# Cree_4x4_Led_Panel.net
KiCad netlist of a schematic drawn in EAGLE
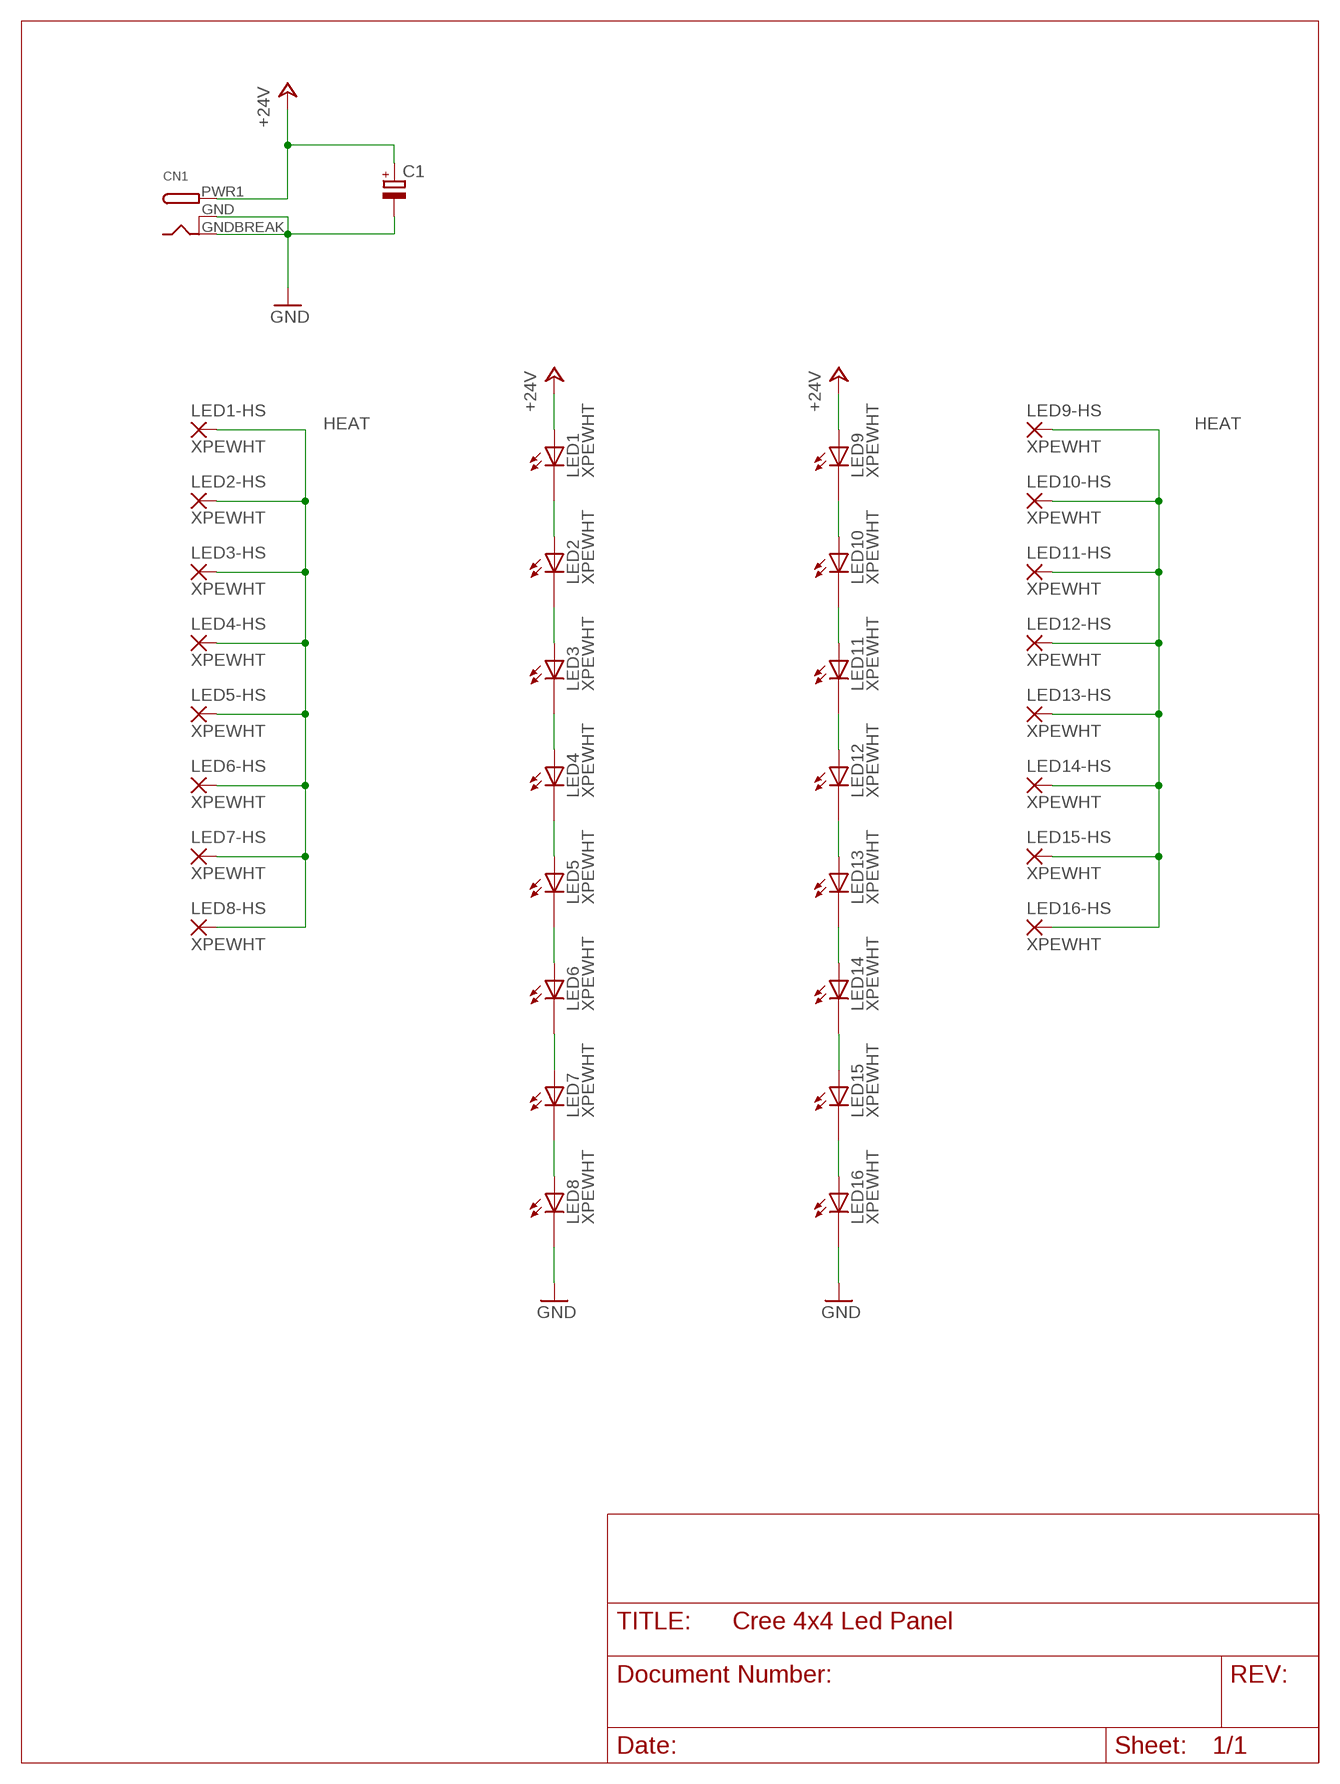
[diagram p0: schematic, sheet 1]

(export (version "E")
  (design (tool "Eeschema 10.0.6"))
  (components
    (comp (ref "C1")
      (value "CPOL-EUSMCC")
      (footprint "eagle-import:SMC_C")
      (libsource (lib "eagle-import") (part "CPOL-EUSMCC"))
    )
    (comp (ref "CN1")
      (value "DCBARRELSMT")
      (footprint "eagle-import:DCJACK_2MM_SMT")
      (libsource (lib "eagle-import") (part "DCBARRELSMT"))
    )
    (comp (ref "LED1")
      (value "XPEWHT")
      (footprint "eagle-import:CREE_XLAMP")
      (libsource (lib "eagle-import") (part "XPEWHT-01-0000-00BC2"))
    )
    (comp (ref "LED2")
      (value "XPEWHT")
      (footprint "eagle-import:CREE_XLAMP")
      (libsource (lib "eagle-import") (part "XPEWHT-01-0000-00BC2"))
    )
    (comp (ref "LED3")
      (value "XPEWHT")
      (footprint "eagle-import:CREE_XLAMP")
      (libsource (lib "eagle-import") (part "XPEWHT-01-0000-00BC2"))
    )
    (comp (ref "LED4")
      (value "XPEWHT")
      (footprint "eagle-import:CREE_XLAMP")
      (libsource (lib "eagle-import") (part "XPEWHT-01-0000-00BC2"))
    )
    (comp (ref "LED5")
      (value "XPEWHT")
      (footprint "eagle-import:CREE_XLAMP")
      (libsource (lib "eagle-import") (part "XPEWHT-01-0000-00BC2"))
    )
    (comp (ref "LED6")
      (value "XPEWHT")
      (footprint "eagle-import:CREE_XLAMP")
      (libsource (lib "eagle-import") (part "XPEWHT-01-0000-00BC2"))
    )
    (comp (ref "LED7")
      (value "XPEWHT")
      (footprint "eagle-import:CREE_XLAMP")
      (libsource (lib "eagle-import") (part "XPEWHT-01-0000-00BC2"))
    )
    (comp (ref "LED8")
      (value "XPEWHT")
      (footprint "eagle-import:CREE_XLAMP")
      (libsource (lib "eagle-import") (part "XPEWHT-01-0000-00BC2"))
    )
    (comp (ref "LED9")
      (value "XPEWHT")
      (footprint "eagle-import:CREE_XLAMP")
      (libsource (lib "eagle-import") (part "XPEWHT-01-0000-00BC2"))
    )
    (comp (ref "LED10")
      (value "XPEWHT")
      (footprint "eagle-import:CREE_XLAMP")
      (libsource (lib "eagle-import") (part "XPEWHT-01-0000-00BC2"))
    )
    (comp (ref "LED11")
      (value "XPEWHT")
      (footprint "eagle-import:CREE_XLAMP")
      (libsource (lib "eagle-import") (part "XPEWHT-01-0000-00BC2"))
    )
    (comp (ref "LED12")
      (value "XPEWHT")
      (footprint "eagle-import:CREE_XLAMP")
      (libsource (lib "eagle-import") (part "XPEWHT-01-0000-00BC2"))
    )
    (comp (ref "LED13")
      (value "XPEWHT")
      (footprint "eagle-import:CREE_XLAMP")
      (libsource (lib "eagle-import") (part "XPEWHT-01-0000-00BC2"))
    )
    (comp (ref "LED14")
      (value "XPEWHT")
      (footprint "eagle-import:CREE_XLAMP")
      (libsource (lib "eagle-import") (part "XPEWHT-01-0000-00BC2"))
    )
    (comp (ref "LED15")
      (value "XPEWHT")
      (footprint "eagle-import:CREE_XLAMP")
      (libsource (lib "eagle-import") (part "XPEWHT-01-0000-00BC2"))
    )
    (comp (ref "LED16")
      (value "XPEWHT")
      (footprint "eagle-import:CREE_XLAMP")
      (libsource (lib "eagle-import") (part "XPEWHT-01-0000-00BC2"))
    )
  )
  (nets
    (net (code "1") (name "+24V") (class "Default")
      (node (ref "C1") (pin "+") (pinfunction "+_+") (pintype "passive"))
      (node (ref "CN1") (pin "PWR1") (pinfunction "PWR_PWR1") (pintype "power_in"))
      (node (ref "LED1") (pin "A") (pinfunction "A_A") (pintype "passive"))
      (node (ref "LED9") (pin "A") (pinfunction "A_A") (pintype "passive"))
    )
    (net (code "2") (name "/HEAT") (class "Default")
      (node (ref "LED1") (pin "X") (pinfunction "P_X") (pintype "passive"))
      (node (ref "LED10") (pin "X") (pinfunction "P_X") (pintype "passive"))
      (node (ref "LED11") (pin "X") (pinfunction "P_X") (pintype "passive"))
      (node (ref "LED12") (pin "X") (pinfunction "P_X") (pintype "passive"))
      (node (ref "LED13") (pin "X") (pinfunction "P_X") (pintype "passive"))
      (node (ref "LED14") (pin "X") (pinfunction "P_X") (pintype "passive"))
      (node (ref "LED15") (pin "X") (pinfunction "P_X") (pintype "passive"))
      (node (ref "LED16") (pin "X") (pinfunction "P_X") (pintype "passive"))
      (node (ref "LED2") (pin "X") (pinfunction "P_X") (pintype "passive"))
      (node (ref "LED3") (pin "X") (pinfunction "P_X") (pintype "passive"))
      (node (ref "LED4") (pin "X") (pinfunction "P_X") (pintype "passive"))
      (node (ref "LED5") (pin "X") (pinfunction "P_X") (pintype "passive"))
      (node (ref "LED6") (pin "X") (pinfunction "P_X") (pintype "passive"))
      (node (ref "LED7") (pin "X") (pinfunction "P_X") (pintype "passive"))
      (node (ref "LED8") (pin "X") (pinfunction "P_X") (pintype "passive"))
      (node (ref "LED9") (pin "X") (pinfunction "P_X") (pintype "passive"))
    )
    (net (code "3") (name "GND") (class "Default")
      (node (ref "C1") (pin "-") (pinfunction "-_-") (pintype "passive"))
      (node (ref "CN1") (pin "GND") (pinfunction "GNDBREAK_GND") (pintype "power_in"))
      (node (ref "CN1") (pin "GNDBREAK") (pinfunction "GND_GNDBREAK") (pintype "power_in"))
      (node (ref "LED16") (pin "C") (pinfunction "C_C") (pintype "passive"))
      (node (ref "LED8") (pin "C") (pinfunction "C_C") (pintype "passive"))
    )
    (net (code "4") (name "Net-(LED1-PadC)") (class "Default")
      (node (ref "LED1") (pin "C") (pinfunction "C_C") (pintype "passive"))
      (node (ref "LED2") (pin "A") (pinfunction "A_A") (pintype "passive"))
    )
    (net (code "5") (name "Net-(LED2-PadC)") (class "Default")
      (node (ref "LED2") (pin "C") (pinfunction "C_C") (pintype "passive"))
      (node (ref "LED3") (pin "A") (pinfunction "A_A") (pintype "passive"))
    )
    (net (code "6") (name "Net-(LED3-PadC)") (class "Default")
      (node (ref "LED3") (pin "C") (pinfunction "C_C") (pintype "passive"))
      (node (ref "LED4") (pin "A") (pinfunction "A_A") (pintype "passive"))
    )
    (net (code "7") (name "Net-(LED4-PadC)") (class "Default")
      (node (ref "LED4") (pin "C") (pinfunction "C_C") (pintype "passive"))
      (node (ref "LED5") (pin "A") (pinfunction "A_A") (pintype "passive"))
    )
    (net (code "8") (name "Net-(LED5-PadC)") (class "Default")
      (node (ref "LED5") (pin "C") (pinfunction "C_C") (pintype "passive"))
      (node (ref "LED6") (pin "A") (pinfunction "A_A") (pintype "passive"))
    )
    (net (code "9") (name "Net-(LED6-PadC)") (class "Default")
      (node (ref "LED6") (pin "C") (pinfunction "C_C") (pintype "passive"))
      (node (ref "LED7") (pin "A") (pinfunction "A_A") (pintype "passive"))
    )
    (net (code "10") (name "Net-(LED7-PadC)") (class "Default")
      (node (ref "LED7") (pin "C") (pinfunction "C_C") (pintype "passive"))
      (node (ref "LED8") (pin "A") (pinfunction "A_A") (pintype "passive"))
    )
    (net (code "11") (name "Net-(LED10-PadA)") (class "Default")
      (node (ref "LED10") (pin "A") (pinfunction "A_A") (pintype "passive"))
      (node (ref "LED9") (pin "C") (pinfunction "C_C") (pintype "passive"))
    )
    (net (code "12") (name "Net-(LED10-PadC)") (class "Default")
      (node (ref "LED10") (pin "C") (pinfunction "C_C") (pintype "passive"))
      (node (ref "LED11") (pin "A") (pinfunction "A_A") (pintype "passive"))
    )
    (net (code "13") (name "Net-(LED11-PadC)") (class "Default")
      (node (ref "LED11") (pin "C") (pinfunction "C_C") (pintype "passive"))
      (node (ref "LED12") (pin "A") (pinfunction "A_A") (pintype "passive"))
    )
    (net (code "14") (name "Net-(LED12-PadC)") (class "Default")
      (node (ref "LED12") (pin "C") (pinfunction "C_C") (pintype "passive"))
      (node (ref "LED13") (pin "A") (pinfunction "A_A") (pintype "passive"))
    )
    (net (code "15") (name "Net-(LED13-PadC)") (class "Default")
      (node (ref "LED13") (pin "C") (pinfunction "C_C") (pintype "passive"))
      (node (ref "LED14") (pin "A") (pinfunction "A_A") (pintype "passive"))
    )
    (net (code "16") (name "Net-(LED14-PadC)") (class "Default")
      (node (ref "LED14") (pin "C") (pinfunction "C_C") (pintype "passive"))
      (node (ref "LED15") (pin "A") (pinfunction "A_A") (pintype "passive"))
    )
    (net (code "17") (name "Net-(LED15-PadC)") (class "Default")
      (node (ref "LED15") (pin "C") (pinfunction "C_C") (pintype "passive"))
      (node (ref "LED16") (pin "A") (pinfunction "A_A") (pintype "passive"))
    )
    (net (code "18") (name "unconnected-(LED1B-A-PadA@1)") (class "Default")
      (node (ref "LED1") (pin "A@1") (pinfunction "A_A@1") (pintype "passive"))
    )
    (net (code "19") (name "unconnected-(LED1B-C-PadC@1)") (class "Default")
      (node (ref "LED1") (pin "C@1") (pinfunction "C_C@1") (pintype "passive"))
    )
    (net (code "20") (name "unconnected-(LED2B-A-PadA@1)") (class "Default")
      (node (ref "LED2") (pin "A@1") (pinfunction "A_A@1") (pintype "passive"))
    )
    (net (code "21") (name "unconnected-(LED2B-C-PadC@1)") (class "Default")
      (node (ref "LED2") (pin "C@1") (pinfunction "C_C@1") (pintype "passive"))
    )
    (net (code "22") (name "unconnected-(LED3B-A-PadA@1)") (class "Default")
      (node (ref "LED3") (pin "A@1") (pinfunction "A_A@1") (pintype "passive"))
    )
    (net (code "23") (name "unconnected-(LED3B-C-PadC@1)") (class "Default")
      (node (ref "LED3") (pin "C@1") (pinfunction "C_C@1") (pintype "passive"))
    )
    (net (code "24") (name "unconnected-(LED4B-A-PadA@1)") (class "Default")
      (node (ref "LED4") (pin "A@1") (pinfunction "A_A@1") (pintype "passive"))
    )
    (net (code "25") (name "unconnected-(LED4B-C-PadC@1)") (class "Default")
      (node (ref "LED4") (pin "C@1") (pinfunction "C_C@1") (pintype "passive"))
    )
    (net (code "26") (name "unconnected-(LED5B-A-PadA@1)") (class "Default")
      (node (ref "LED5") (pin "A@1") (pinfunction "A_A@1") (pintype "passive"))
    )
    (net (code "27") (name "unconnected-(LED5B-C-PadC@1)") (class "Default")
      (node (ref "LED5") (pin "C@1") (pinfunction "C_C@1") (pintype "passive"))
    )
    (net (code "28") (name "unconnected-(LED6B-A-PadA@1)") (class "Default")
      (node (ref "LED6") (pin "A@1") (pinfunction "A_A@1") (pintype "passive"))
    )
    (net (code "29") (name "unconnected-(LED6B-C-PadC@1)") (class "Default")
      (node (ref "LED6") (pin "C@1") (pinfunction "C_C@1") (pintype "passive"))
    )
    (net (code "30") (name "unconnected-(LED7B-A-PadA@1)") (class "Default")
      (node (ref "LED7") (pin "A@1") (pinfunction "A_A@1") (pintype "passive"))
    )
    (net (code "31") (name "unconnected-(LED7B-C-PadC@1)") (class "Default")
      (node (ref "LED7") (pin "C@1") (pinfunction "C_C@1") (pintype "passive"))
    )
    (net (code "32") (name "unconnected-(LED8B-A-PadA@1)") (class "Default")
      (node (ref "LED8") (pin "A@1") (pinfunction "A_A@1") (pintype "passive"))
    )
    (net (code "33") (name "unconnected-(LED8B-C-PadC@1)") (class "Default")
      (node (ref "LED8") (pin "C@1") (pinfunction "C_C@1") (pintype "passive"))
    )
    (net (code "34") (name "unconnected-(LED9B-A-PadA@1)") (class "Default")
      (node (ref "LED9") (pin "A@1") (pinfunction "A_A@1") (pintype "passive"))
    )
    (net (code "35") (name "unconnected-(LED9B-C-PadC@1)") (class "Default")
      (node (ref "LED9") (pin "C@1") (pinfunction "C_C@1") (pintype "passive"))
    )
    (net (code "36") (name "unconnected-(LED10B-A-PadA@1)") (class "Default")
      (node (ref "LED10") (pin "A@1") (pinfunction "A_A@1") (pintype "passive"))
    )
    (net (code "37") (name "unconnected-(LED10B-C-PadC@1)") (class "Default")
      (node (ref "LED10") (pin "C@1") (pinfunction "C_C@1") (pintype "passive"))
    )
    (net (code "38") (name "unconnected-(LED11B-A-PadA@1)") (class "Default")
      (node (ref "LED11") (pin "A@1") (pinfunction "A_A@1") (pintype "passive"))
    )
    (net (code "39") (name "unconnected-(LED11B-C-PadC@1)") (class "Default")
      (node (ref "LED11") (pin "C@1") (pinfunction "C_C@1") (pintype "passive"))
    )
    (net (code "40") (name "unconnected-(LED12B-A-PadA@1)") (class "Default")
      (node (ref "LED12") (pin "A@1") (pinfunction "A_A@1") (pintype "passive"))
    )
    (net (code "41") (name "unconnected-(LED12B-C-PadC@1)") (class "Default")
      (node (ref "LED12") (pin "C@1") (pinfunction "C_C@1") (pintype "passive"))
    )
    (net (code "42") (name "unconnected-(LED13B-A-PadA@1)") (class "Default")
      (node (ref "LED13") (pin "A@1") (pinfunction "A_A@1") (pintype "passive"))
    )
    (net (code "43") (name "unconnected-(LED13B-C-PadC@1)") (class "Default")
      (node (ref "LED13") (pin "C@1") (pinfunction "C_C@1") (pintype "passive"))
    )
    (net (code "44") (name "unconnected-(LED14B-A-PadA@1)") (class "Default")
      (node (ref "LED14") (pin "A@1") (pinfunction "A_A@1") (pintype "passive"))
    )
    (net (code "45") (name "unconnected-(LED14B-C-PadC@1)") (class "Default")
      (node (ref "LED14") (pin "C@1") (pinfunction "C_C@1") (pintype "passive"))
    )
    (net (code "46") (name "unconnected-(LED15B-A-PadA@1)") (class "Default")
      (node (ref "LED15") (pin "A@1") (pinfunction "A_A@1") (pintype "passive"))
    )
    (net (code "47") (name "unconnected-(LED15B-C-PadC@1)") (class "Default")
      (node (ref "LED15") (pin "C@1") (pinfunction "C_C@1") (pintype "passive"))
    )
    (net (code "48") (name "unconnected-(LED16B-A-PadA@1)") (class "Default")
      (node (ref "LED16") (pin "A@1") (pinfunction "A_A@1") (pintype "passive"))
    )
    (net (code "49") (name "unconnected-(LED16B-C-PadC@1)") (class "Default")
      (node (ref "LED16") (pin "C@1") (pinfunction "C_C@1") (pintype "passive"))
    )
  )
)
